# PAH_Deployments.net
KiCad netlist of a schematic drawn in Altium Designer
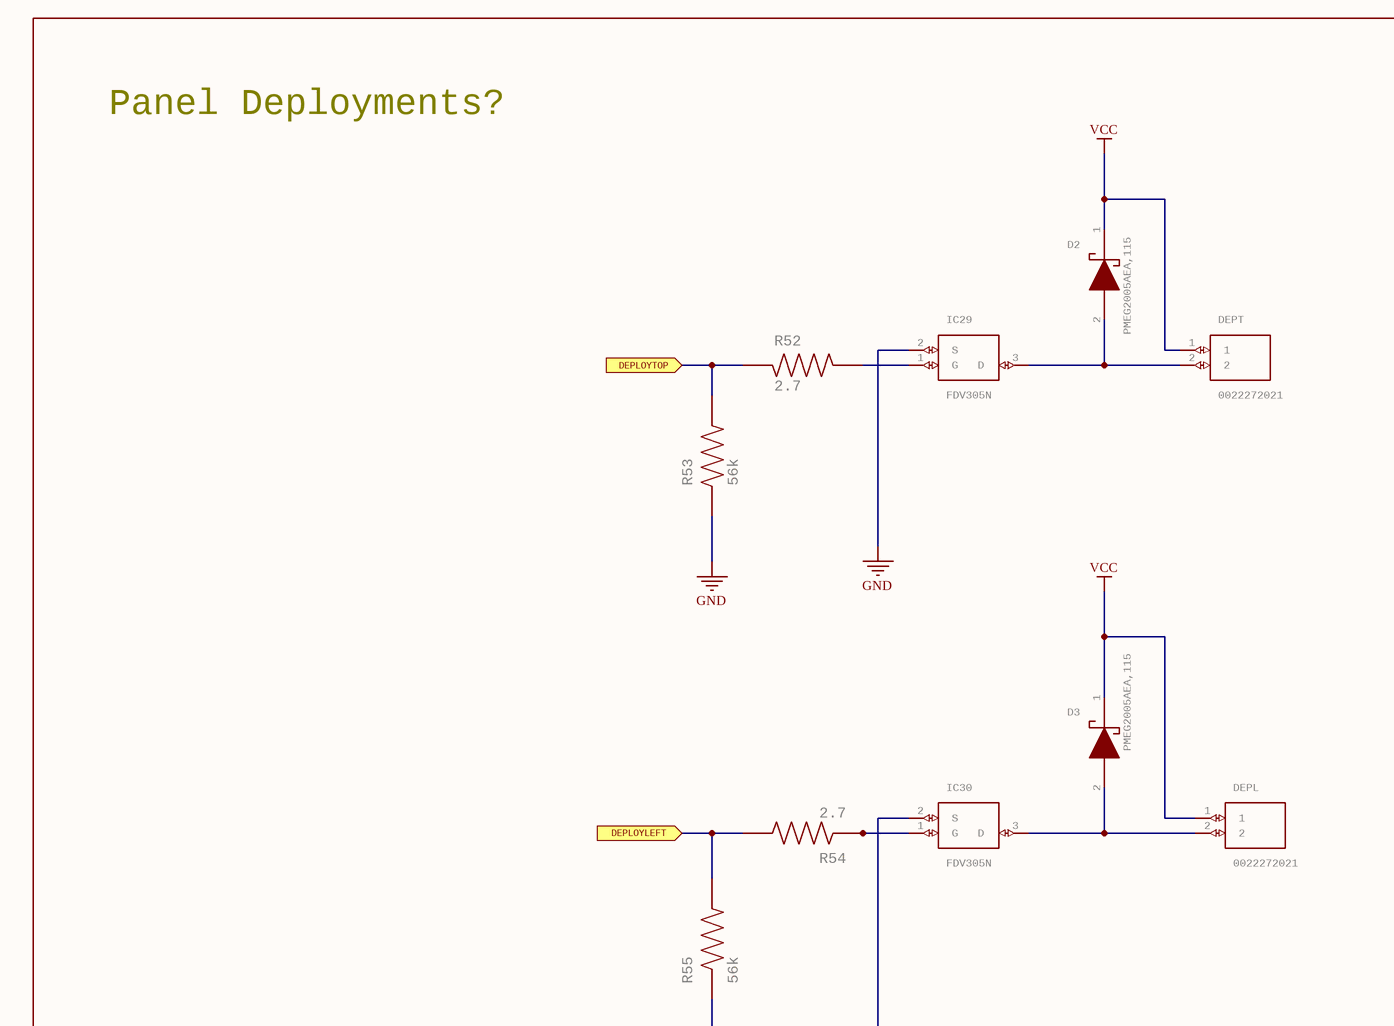
[diagram p0: PAH_Deployments.SchDoc, top left]
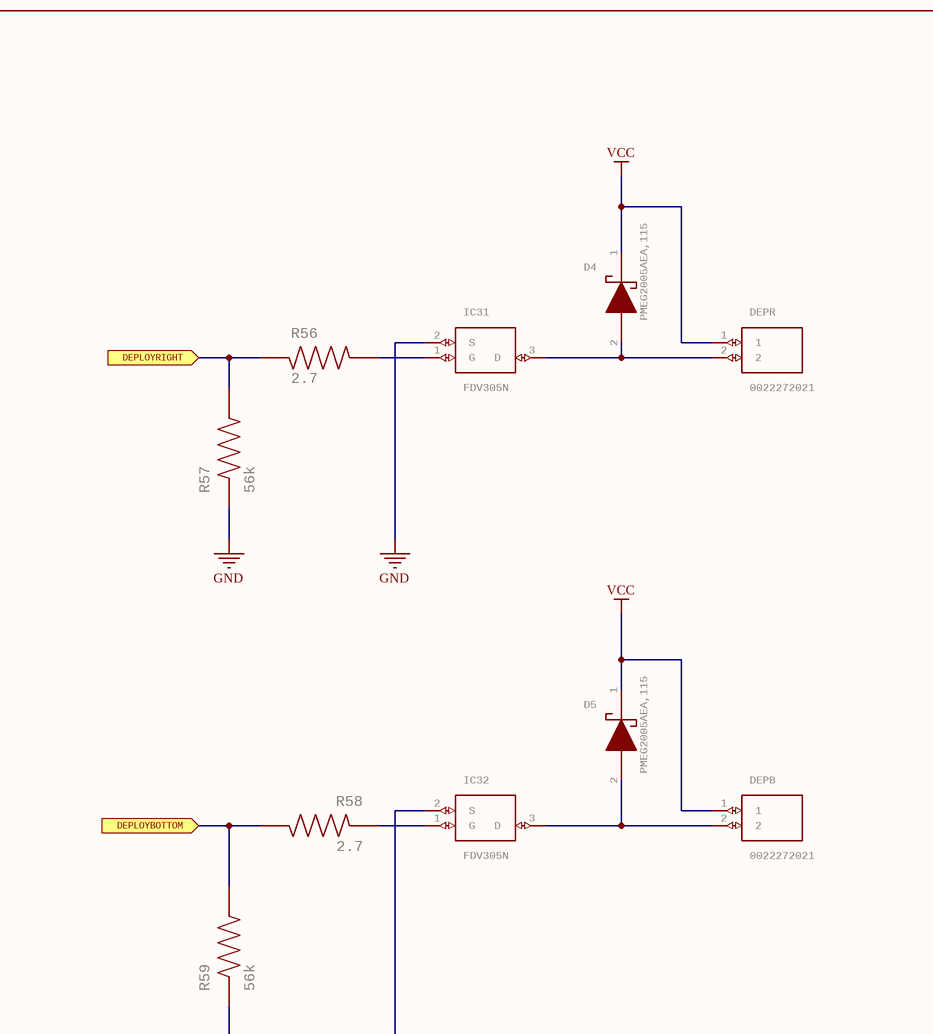
[diagram p1: PAH_Deployments.SchDoc, top right]
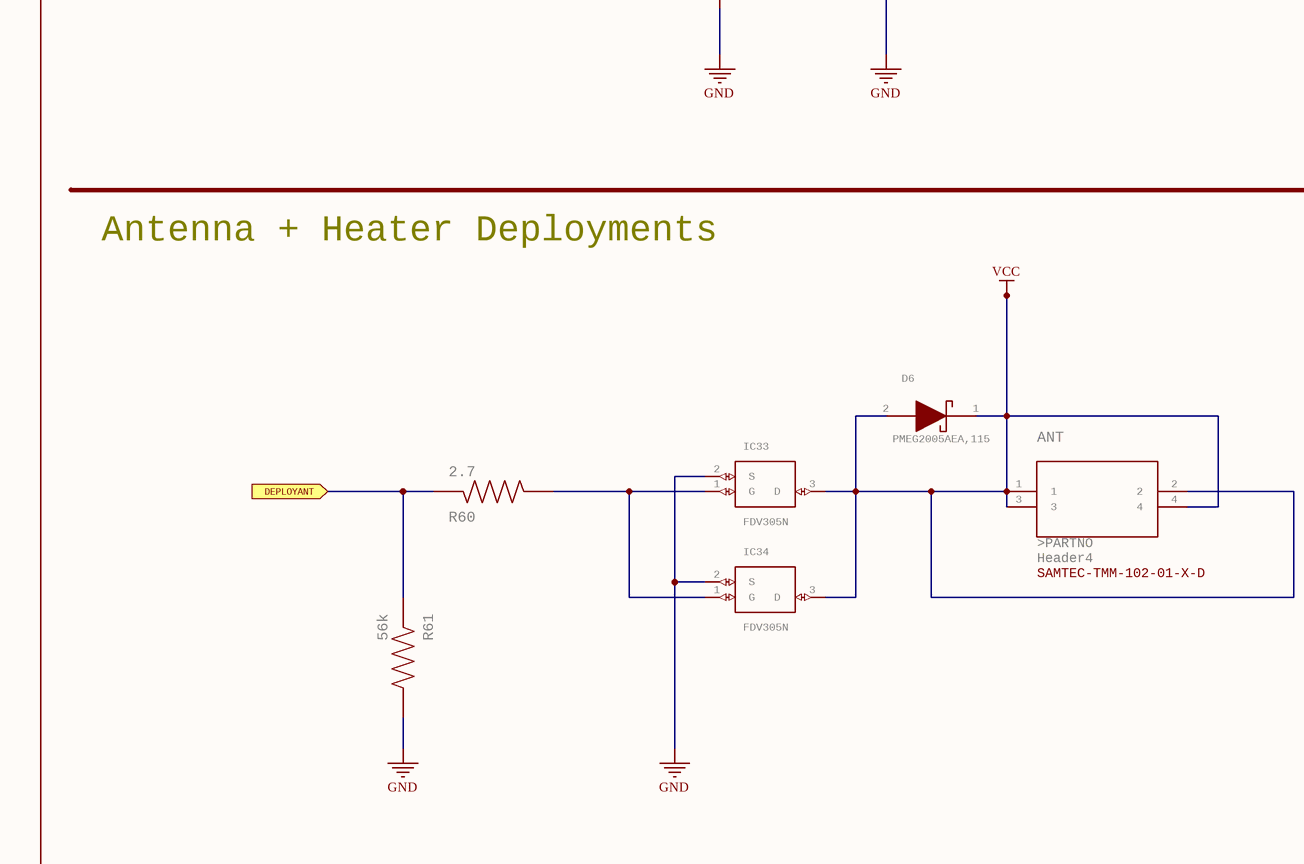
[diagram p2: PAH_Deployments.SchDoc, bottom left]
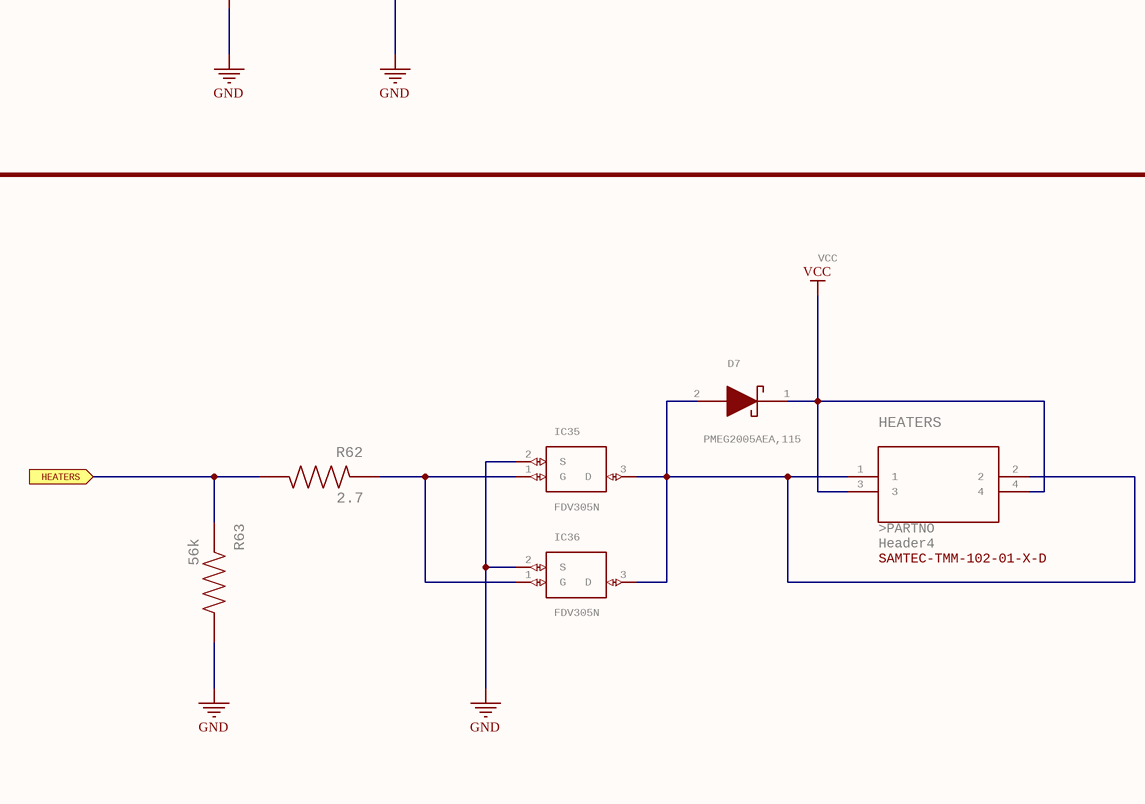
[diagram p3: PAH_Deployments.SchDoc, bottom right]

(export (version "E")
  (design (tool "Eeschema 10.0.6"))
  (components
    (comp (ref "ANT")
      (value "Header4")
      (footprint "SAMTEC-TMM-102-01-X-D")
      (description "Check prices")
      (fields
        (field (name "PARTNO") ">PARTNO")
        (field (name "SAMTEC-TMM-102-01-X-D") "SAMTEC-TMM-102-01-X-D")
        (field (name "MF") "Samtec Inc.")
        (field (name "MP") "TMM-102-01-T-D")
        (field (name "LIBRARYNAME") "4 pin header replace")
      )
      (libsource (lib "4 pin header replace") (part "SAMTEC-TMM-102-01-X-DJ"))
    )
    (comp (ref "D2")
      (value "PMEG2005AEA,115")
      (footprint "SOD2512X110N")
      (description "NXP PMEG2005AEA,115, SMT Schottky Diode, 20V 500mA, 2-Pin SOD-323   Source:  Datasheet")
      (fields (field (name "MOUSER_PART_NUMBER") "771-PMEG2005AEA115"))
      (libsource (lib "PMEG2005AEA_115") (part "PMEG2005AEA,115"))
    )
    (comp (ref "D3")
      (value "PMEG2005AEA,115")
      (footprint "SOD2512X110N")
      (description "NXP PMEG2005AEA,115, SMT Schottky Diode, 20V 500mA, 2-Pin SOD-323   Source:  Datasheet")
      (fields (field (name "MOUSER_PART_NUMBER") "771-PMEG2005AEA115"))
      (libsource (lib "PMEG2005AEA_115") (part "PMEG2005AEA,115"))
    )
    (comp (ref "D4")
      (value "PMEG2005AEA,115")
      (footprint "SOD2512X110N")
      (description "NXP PMEG2005AEA,115, SMT Schottky Diode, 20V 500mA, 2-Pin SOD-323   Source:  Datasheet")
      (fields (field (name "MOUSER_PART_NUMBER") "771-PMEG2005AEA115"))
      (libsource (lib "PMEG2005AEA_115") (part "PMEG2005AEA,115"))
    )
    (comp (ref "D5")
      (value "PMEG2005AEA,115")
      (footprint "SOD2512X110N")
      (description "NXP PMEG2005AEA,115, SMT Schottky Diode, 20V 500mA, 2-Pin SOD-323   Source:  Datasheet")
      (fields (field (name "MOUSER_PART_NUMBER") "771-PMEG2005AEA115"))
      (libsource (lib "PMEG2005AEA_115") (part "PMEG2005AEA,115"))
    )
    (comp (ref "D6")
      (value "PMEG2005AEA,115")
      (footprint "SOD2512X110N")
      (description "NXP PMEG2005AEA,115, SMT Schottky Diode, 20V 500mA, 2-Pin SOD-323   Source:  Datasheet")
      (fields (field (name "MOUSER_PART_NUMBER") "771-PMEG2005AEA115"))
      (libsource (lib "PMEG2005AEA_115") (part "PMEG2005AEA,115"))
    )
    (comp (ref "D7")
      (value "PMEG2005AEA,115")
      (footprint "SOD2512X110N")
      (description "NXP PMEG2005AEA,115, SMT Schottky Diode, 20V 500mA, 2-Pin SOD-323   Source:  Datasheet")
      (fields (field (name "MOUSER_PART_NUMBER") "771-PMEG2005AEA115"))
      (libsource (lib "PMEG2005AEA_115") (part "PMEG2005AEA,115"))
    )
    (comp (ref "DEPB")
      (value "0022272021")
      (footprint "SHDR2W64P0X254_1X2_508X580X117")
      (description "Conn Wire to Board HDR 2 POS 2.54mm Solder ST Thru-Hole KK Bag   Source:  Datasheet")
      (libsource (lib "header 2") (part "0022272021"))
    )
    (comp (ref "DEPL")
      (value "0022272021")
      (footprint "SHDR2W64P0X254_1X2_508X580X117")
      (description "Conn Wire to Board HDR 2 POS 2.54mm Solder ST Thru-Hole KK Bag   Source:  Datasheet")
      (libsource (lib "header 2") (part "0022272021"))
    )
    (comp (ref "DEPR")
      (value "0022272021")
      (footprint "SHDR2W64P0X254_1X2_508X580X117")
      (description "Conn Wire to Board HDR 2 POS 2.54mm Solder ST Thru-Hole KK Bag   Source:  Datasheet")
      (libsource (lib "header 2") (part "0022272021"))
    )
    (comp (ref "DEPT")
      (value "0022272021")
      (footprint "SHDR2W64P0X254_1X2_508X580X117")
      (description "Conn Wire to Board HDR 2 POS 2.54mm Solder ST Thru-Hole KK Bag   Source:  Datasheet")
      (libsource (lib "header 2") (part "0022272021"))
    )
    (comp (ref "HEATERS")
      (value "Header4")
      (footprint "SAMTEC-TMM-102-01-X-D")
      (description "Check prices")
      (fields
        (field (name "PARTNO") ">PARTNO")
        (field (name "SAMTEC-TMM-102-01-X-D") "SAMTEC-TMM-102-01-X-D")
        (field (name "MF") "Samtec Inc.")
        (field (name "MP") "TMM-102-01-T-D")
        (field (name "LIBRARYNAME") "4 pin header replace")
      )
      (libsource (lib "4 pin header replace") (part "SAMTEC-TMM-102-01-X-DJ"))
    )
    (comp (ref "IC29")
      (value "FDV305N")
      (footprint "SOT95P240X120-3N")
      (description "FDV305N, N-channel MOSFET Transistor 0.9 A 20 V, 3-Pin SOT-23   Source:  Datasheet")
      (fields (field (name "MOUSER_PART_NUMBER") "512-FDV305N"))
      (libsource (lib "FDV305N") (part "FDV305N"))
    )
    (comp (ref "IC30")
      (value "FDV305N")
      (footprint "SOT95P240X120-3N")
      (description "FDV305N, N-channel MOSFET Transistor 0.9 A 20 V, 3-Pin SOT-23   Source:  Datasheet")
      (fields (field (name "MOUSER_PART_NUMBER") "512-FDV305N"))
      (libsource (lib "FDV305N") (part "FDV305N"))
    )
    (comp (ref "IC31")
      (value "FDV305N")
      (footprint "SOT95P240X120-3N")
      (description "FDV305N, N-channel MOSFET Transistor 0.9 A 20 V, 3-Pin SOT-23   Source:  Datasheet")
      (fields (field (name "MOUSER_PART_NUMBER") "512-FDV305N"))
      (libsource (lib "FDV305N") (part "FDV305N"))
    )
    (comp (ref "IC32")
      (value "FDV305N")
      (footprint "SOT95P240X120-3N")
      (description "FDV305N, N-channel MOSFET Transistor 0.9 A 20 V, 3-Pin SOT-23   Source:  Datasheet")
      (fields (field (name "MOUSER_PART_NUMBER") "512-FDV305N"))
      (libsource (lib "FDV305N") (part "FDV305N"))
    )
    (comp (ref "IC33")
      (value "FDV305N")
      (footprint "SOT95P240X120-3N")
      (description "FDV305N, N-channel MOSFET Transistor 0.9 A 20 V, 3-Pin SOT-23   Source:  Datasheet")
      (fields (field (name "MOUSER_PART_NUMBER") "512-FDV305N"))
      (libsource (lib "FDV305N") (part "FDV305N"))
    )
    (comp (ref "IC34")
      (value "FDV305N")
      (footprint "SOT95P240X120-3N")
      (description "FDV305N, N-channel MOSFET Transistor 0.9 A 20 V, 3-Pin SOT-23   Source:  Datasheet")
      (fields (field (name "MOUSER_PART_NUMBER") "512-FDV305N"))
      (libsource (lib "FDV305N") (part "FDV305N"))
    )
    (comp (ref "IC35")
      (value "FDV305N")
      (footprint "SOT95P240X120-3N")
      (description "FDV305N, N-channel MOSFET Transistor 0.9 A 20 V, 3-Pin SOT-23   Source:  Datasheet")
      (fields (field (name "MOUSER_PART_NUMBER") "512-FDV305N"))
      (libsource (lib "FDV305N") (part "FDV305N"))
    )
    (comp (ref "IC36")
      (value "FDV305N")
      (footprint "SOT95P240X120-3N")
      (description "FDV305N, N-channel MOSFET Transistor 0.9 A 20 V, 3-Pin SOT-23   Source:  Datasheet")
      (fields (field (name "MOUSER_PART_NUMBER") "512-FDV305N"))
      (libsource (lib "FDV305N") (part "FDV305N"))
    )
    (comp (ref "R52")
      (value "2.7")
      (footprint "RESC1608X55N")
      (fields
        (field (name "DIGI-KEY_PART_NUMBER") "DIGI-KEY_PART_NUMBER")
        (field (name "MF") "Susumu")
        (field (name "MP") "RL0816S-2R7-F")
      )
      (libsource (lib "Res1-2.7") (part "RL0816S-2R7-F"))
    )
    (comp (ref "R53")
      (value "56k")
      (footprint "RESC1608X55N")
      (description "RES SMD 56K OHM 0.5% 1/5W 0603")
      (fields (field (name "DIGI-KEY_PART_NUMBER") "DIGI-KEY_PART_NUMBER") (field (name "MF") "Panasonic"))
      (libsource (lib "Res1 56k") (part "ERJ-PB3D5602V"))
    )
    (comp (ref "R54")
      (value "2.7")
      (footprint "RESC1608X55N")
      (fields
        (field (name "DIGI-KEY_PART_NUMBER") "DIGI-KEY_PART_NUMBER")
        (field (name "MF") "Susumu")
        (field (name "MP") "RL0816S-2R7-F")
      )
      (libsource (lib "Res1-2.7") (part "RL0816S-2R7-F"))
    )
    (comp (ref "R55")
      (value "56k")
      (footprint "RESC1608X55N")
      (description "RES SMD 56K OHM 0.5% 1/5W 0603")
      (fields (field (name "DIGI-KEY_PART_NUMBER") "DIGI-KEY_PART_NUMBER") (field (name "MF") "Panasonic"))
      (libsource (lib "Res1 56k") (part "ERJ-PB3D5602V"))
    )
    (comp (ref "R56")
      (value "2.7")
      (footprint "RESC1608X55N")
      (fields
        (field (name "DIGI-KEY_PART_NUMBER") "DIGI-KEY_PART_NUMBER")
        (field (name "MF") "Susumu")
        (field (name "MP") "RL0816S-2R7-F")
      )
      (libsource (lib "Res1-2.7") (part "RL0816S-2R7-F"))
    )
    (comp (ref "R57")
      (value "56k")
      (footprint "RESC1608X55N")
      (description "RES SMD 56K OHM 0.5% 1/5W 0603")
      (fields (field (name "DIGI-KEY_PART_NUMBER") "DIGI-KEY_PART_NUMBER") (field (name "MF") "Panasonic"))
      (libsource (lib "Res1 56k") (part "ERJ-PB3D5602V"))
    )
    (comp (ref "R58")
      (value "2.7")
      (footprint "RESC1608X55N")
      (fields
        (field (name "DIGI-KEY_PART_NUMBER") "DIGI-KEY_PART_NUMBER")
        (field (name "MF") "Susumu")
        (field (name "MP") "RL0816S-2R7-F")
      )
      (libsource (lib "Res1-2.7") (part "RL0816S-2R7-F"))
    )
    (comp (ref "R59")
      (value "56k")
      (footprint "RESC1608X55N")
      (description "RES SMD 56K OHM 0.5% 1/5W 0603")
      (fields (field (name "DIGI-KEY_PART_NUMBER") "DIGI-KEY_PART_NUMBER") (field (name "MF") "Panasonic"))
      (libsource (lib "Res1 56k") (part "ERJ-PB3D5602V"))
    )
    (comp (ref "R60")
      (value "2.7")
      (footprint "RESC1608X55N")
      (fields
        (field (name "DIGI-KEY_PART_NUMBER") "DIGI-KEY_PART_NUMBER")
        (field (name "MF") "Susumu")
        (field (name "MP") "RL0816S-2R7-F")
      )
      (libsource (lib "Res1-2.7") (part "RL0816S-2R7-F"))
    )
    (comp (ref "R61")
      (value "56k")
      (footprint "RESC1608X55N")
      (description "RES SMD 56K OHM 0.5% 1/5W 0603")
      (fields (field (name "DIGI-KEY_PART_NUMBER") "DIGI-KEY_PART_NUMBER") (field (name "MF") "Panasonic"))
      (libsource (lib "Res1 56k") (part "ERJ-PB3D5602V"))
    )
    (comp (ref "R62")
      (value "2.7")
      (footprint "RESC1608X55N")
      (fields
        (field (name "DIGI-KEY_PART_NUMBER") "DIGI-KEY_PART_NUMBER")
        (field (name "MF") "Susumu")
        (field (name "MP") "RL0816S-2R7-F")
      )
      (libsource (lib "Res1-2.7") (part "RL0816S-2R7-F"))
    )
    (comp (ref "R63")
      (value "56k")
      (footprint "RESC1608X55N")
      (description "RES SMD 56K OHM 0.5% 1/5W 0603")
      (fields (field (name "DIGI-KEY_PART_NUMBER") "DIGI-KEY_PART_NUMBER") (field (name "MF") "Panasonic"))
      (libsource (lib "Res1 56k") (part "ERJ-PB3D5602V"))
    )
  )
  (nets
    (net (code "1") (name "/DEPLOYANT") (class "Default")
      (node (ref "R60") (pin "1") (pinfunction "1_1") (pintype "passive"))
      (node (ref "R61") (pin "1") (pinfunction "1_1") (pintype "passive"))
    )
    (net (code "2") (name "/DEPLOYBOTTOM") (class "Default")
      (node (ref "R58") (pin "2") (pinfunction "2_2") (pintype "passive"))
      (node (ref "R59") (pin "2") (pinfunction "2_2") (pintype "passive"))
    )
    (net (code "3") (name "/DEPLOYLEFT") (class "Default")
      (node (ref "R54") (pin "2") (pinfunction "2_2") (pintype "passive"))
      (node (ref "R55") (pin "2") (pinfunction "2_2") (pintype "passive"))
    )
    (net (code "4") (name "/DEPLOYRIGHT") (class "Default")
      (node (ref "R56") (pin "2") (pinfunction "2_2") (pintype "passive"))
      (node (ref "R57") (pin "2") (pinfunction "2_2") (pintype "passive"))
    )
    (net (code "5") (name "/DEPLOYTOP") (class "Default")
      (node (ref "R52") (pin "2") (pinfunction "2_2") (pintype "passive"))
      (node (ref "R53") (pin "2") (pinfunction "2_2") (pintype "passive"))
    )
    (net (code "6") (name "/HEATERS") (class "Default")
      (node (ref "R62") (pin "2") (pinfunction "2_2") (pintype "passive"))
      (node (ref "R63") (pin "1") (pinfunction "1_1") (pintype "passive"))
    )
    (net (code "7") (name "GND") (class "Default")
      (node (ref "IC29") (pin "2") (pinfunction "S_2") (pintype "bidirectional"))
      (node (ref "IC30") (pin "2") (pinfunction "S_2") (pintype "bidirectional"))
      (node (ref "IC31") (pin "2") (pinfunction "S_2") (pintype "bidirectional"))
      (node (ref "IC32") (pin "2") (pinfunction "S_2") (pintype "bidirectional"))
      (node (ref "IC33") (pin "2") (pinfunction "S_2") (pintype "bidirectional"))
      (node (ref "IC34") (pin "2") (pinfunction "S_2") (pintype "bidirectional"))
      (node (ref "IC35") (pin "2") (pinfunction "S_2") (pintype "bidirectional"))
      (node (ref "IC36") (pin "2") (pinfunction "S_2") (pintype "bidirectional"))
      (node (ref "R53") (pin "1") (pinfunction "1_1") (pintype "passive"))
      (node (ref "R55") (pin "1") (pinfunction "1_1") (pintype "passive"))
      (node (ref "R57") (pin "1") (pinfunction "1_1") (pintype "passive"))
      (node (ref "R59") (pin "1") (pinfunction "1_1") (pintype "passive"))
      (node (ref "R61") (pin "2") (pinfunction "2_2") (pintype "passive"))
      (node (ref "R63") (pin "2") (pinfunction "2_2") (pintype "passive"))
    )
    (net (code "8") (name "Net-(D2-A)") (class "Default")
      (node (ref "D2") (pin "2") (pinfunction "A_2") (pintype "bidirectional"))
      (node (ref "DEPT") (pin "2") (pinfunction "2_2") (pintype "bidirectional"))
      (node (ref "IC29") (pin "3") (pinfunction "D_3") (pintype "bidirectional"))
    )
    (net (code "9") (name "Net-(D3-A)") (class "Default")
      (node (ref "D3") (pin "2") (pinfunction "A_2") (pintype "bidirectional"))
      (node (ref "DEPL") (pin "2") (pinfunction "2_2") (pintype "bidirectional"))
      (node (ref "IC30") (pin "3") (pinfunction "D_3") (pintype "bidirectional"))
    )
    (net (code "10") (name "Net-(D4-A)") (class "Default")
      (node (ref "D4") (pin "2") (pinfunction "A_2") (pintype "bidirectional"))
      (node (ref "DEPR") (pin "2") (pinfunction "2_2") (pintype "bidirectional"))
      (node (ref "IC31") (pin "3") (pinfunction "D_3") (pintype "bidirectional"))
    )
    (net (code "11") (name "Net-(D5-A)") (class "Default")
      (node (ref "D5") (pin "2") (pinfunction "A_2") (pintype "bidirectional"))
      (node (ref "DEPB") (pin "2") (pinfunction "2_2") (pintype "bidirectional"))
      (node (ref "IC32") (pin "3") (pinfunction "D_3") (pintype "bidirectional"))
    )
    (net (code "12") (name "Net-(D7-A)") (class "Default")
      (node (ref "D7") (pin "2") (pinfunction "A_2") (pintype "bidirectional"))
      (node (ref "HEATERS") (pin "1") (pinfunction "1_1") (pintype "passive"))
      (node (ref "HEATERS") (pin "2") (pinfunction "2_2") (pintype "passive"))
      (node (ref "IC35") (pin "3") (pinfunction "D_3") (pintype "bidirectional"))
      (node (ref "IC36") (pin "3") (pinfunction "D_3") (pintype "bidirectional"))
    )
    (net (code "13") (name "Net-(IC29-G)") (class "Default")
      (node (ref "IC29") (pin "1") (pinfunction "G_1") (pintype "bidirectional"))
      (node (ref "R52") (pin "1") (pinfunction "1_1") (pintype "passive"))
    )
    (net (code "14") (name "Net-(IC30-G)") (class "Default")
      (node (ref "IC30") (pin "1") (pinfunction "G_1") (pintype "bidirectional"))
      (node (ref "R54") (pin "1") (pinfunction "1_1") (pintype "passive"))
    )
    (net (code "15") (name "Net-(IC31-G)") (class "Default")
      (node (ref "IC31") (pin "1") (pinfunction "G_1") (pintype "bidirectional"))
      (node (ref "R56") (pin "1") (pinfunction "1_1") (pintype "passive"))
    )
    (net (code "16") (name "Net-(IC32-G)") (class "Default")
      (node (ref "IC32") (pin "1") (pinfunction "G_1") (pintype "bidirectional"))
      (node (ref "R58") (pin "1") (pinfunction "1_1") (pintype "passive"))
    )
    (net (code "17") (name "Net-(IC33-G)") (class "Default")
      (node (ref "IC33") (pin "1") (pinfunction "G_1") (pintype "bidirectional"))
      (node (ref "IC34") (pin "1") (pinfunction "G_1") (pintype "bidirectional"))
      (node (ref "R60") (pin "2") (pinfunction "2_2") (pintype "passive"))
    )
    (net (code "18") (name "Net-(IC35-G)") (class "Default")
      (node (ref "IC35") (pin "1") (pinfunction "G_1") (pintype "bidirectional"))
      (node (ref "IC36") (pin "1") (pinfunction "G_1") (pintype "bidirectional"))
      (node (ref "R62") (pin "1") (pinfunction "1_1") (pintype "passive"))
    )
    (net (code "19") (name "VCC") (class "Default")
      (node (ref "ANT") (pin "1") (pinfunction "1_1") (pintype "passive"))
      (node (ref "ANT") (pin "2") (pinfunction "2_2") (pintype "passive"))
      (node (ref "ANT") (pin "3") (pinfunction "3_3") (pintype "passive"))
      (node (ref "ANT") (pin "4") (pinfunction "4_4") (pintype "passive"))
      (node (ref "D2") (pin "1") (pinfunction "K_1") (pintype "bidirectional"))
      (node (ref "D3") (pin "1") (pinfunction "K_1") (pintype "bidirectional"))
      (node (ref "D4") (pin "1") (pinfunction "K_1") (pintype "bidirectional"))
      (node (ref "D5") (pin "1") (pinfunction "K_1") (pintype "bidirectional"))
      (node (ref "D6") (pin "1") (pinfunction "K_1") (pintype "bidirectional"))
      (node (ref "D6") (pin "2") (pinfunction "A_2") (pintype "bidirectional"))
      (node (ref "D7") (pin "1") (pinfunction "K_1") (pintype "bidirectional"))
      (node (ref "DEPB") (pin "1") (pinfunction "1_1") (pintype "bidirectional"))
      (node (ref "DEPL") (pin "1") (pinfunction "1_1") (pintype "bidirectional"))
      (node (ref "DEPR") (pin "1") (pinfunction "1_1") (pintype "bidirectional"))
      (node (ref "DEPT") (pin "1") (pinfunction "1_1") (pintype "bidirectional"))
      (node (ref "HEATERS") (pin "3") (pinfunction "3_3") (pintype "passive"))
      (node (ref "HEATERS") (pin "4") (pinfunction "4_4") (pintype "passive"))
      (node (ref "IC33") (pin "3") (pinfunction "D_3") (pintype "bidirectional"))
      (node (ref "IC34") (pin "3") (pinfunction "D_3") (pintype "bidirectional"))
    )
  )
)
